# 04-BLE.net
KiCad netlist of a schematic drawn in Altium Designer
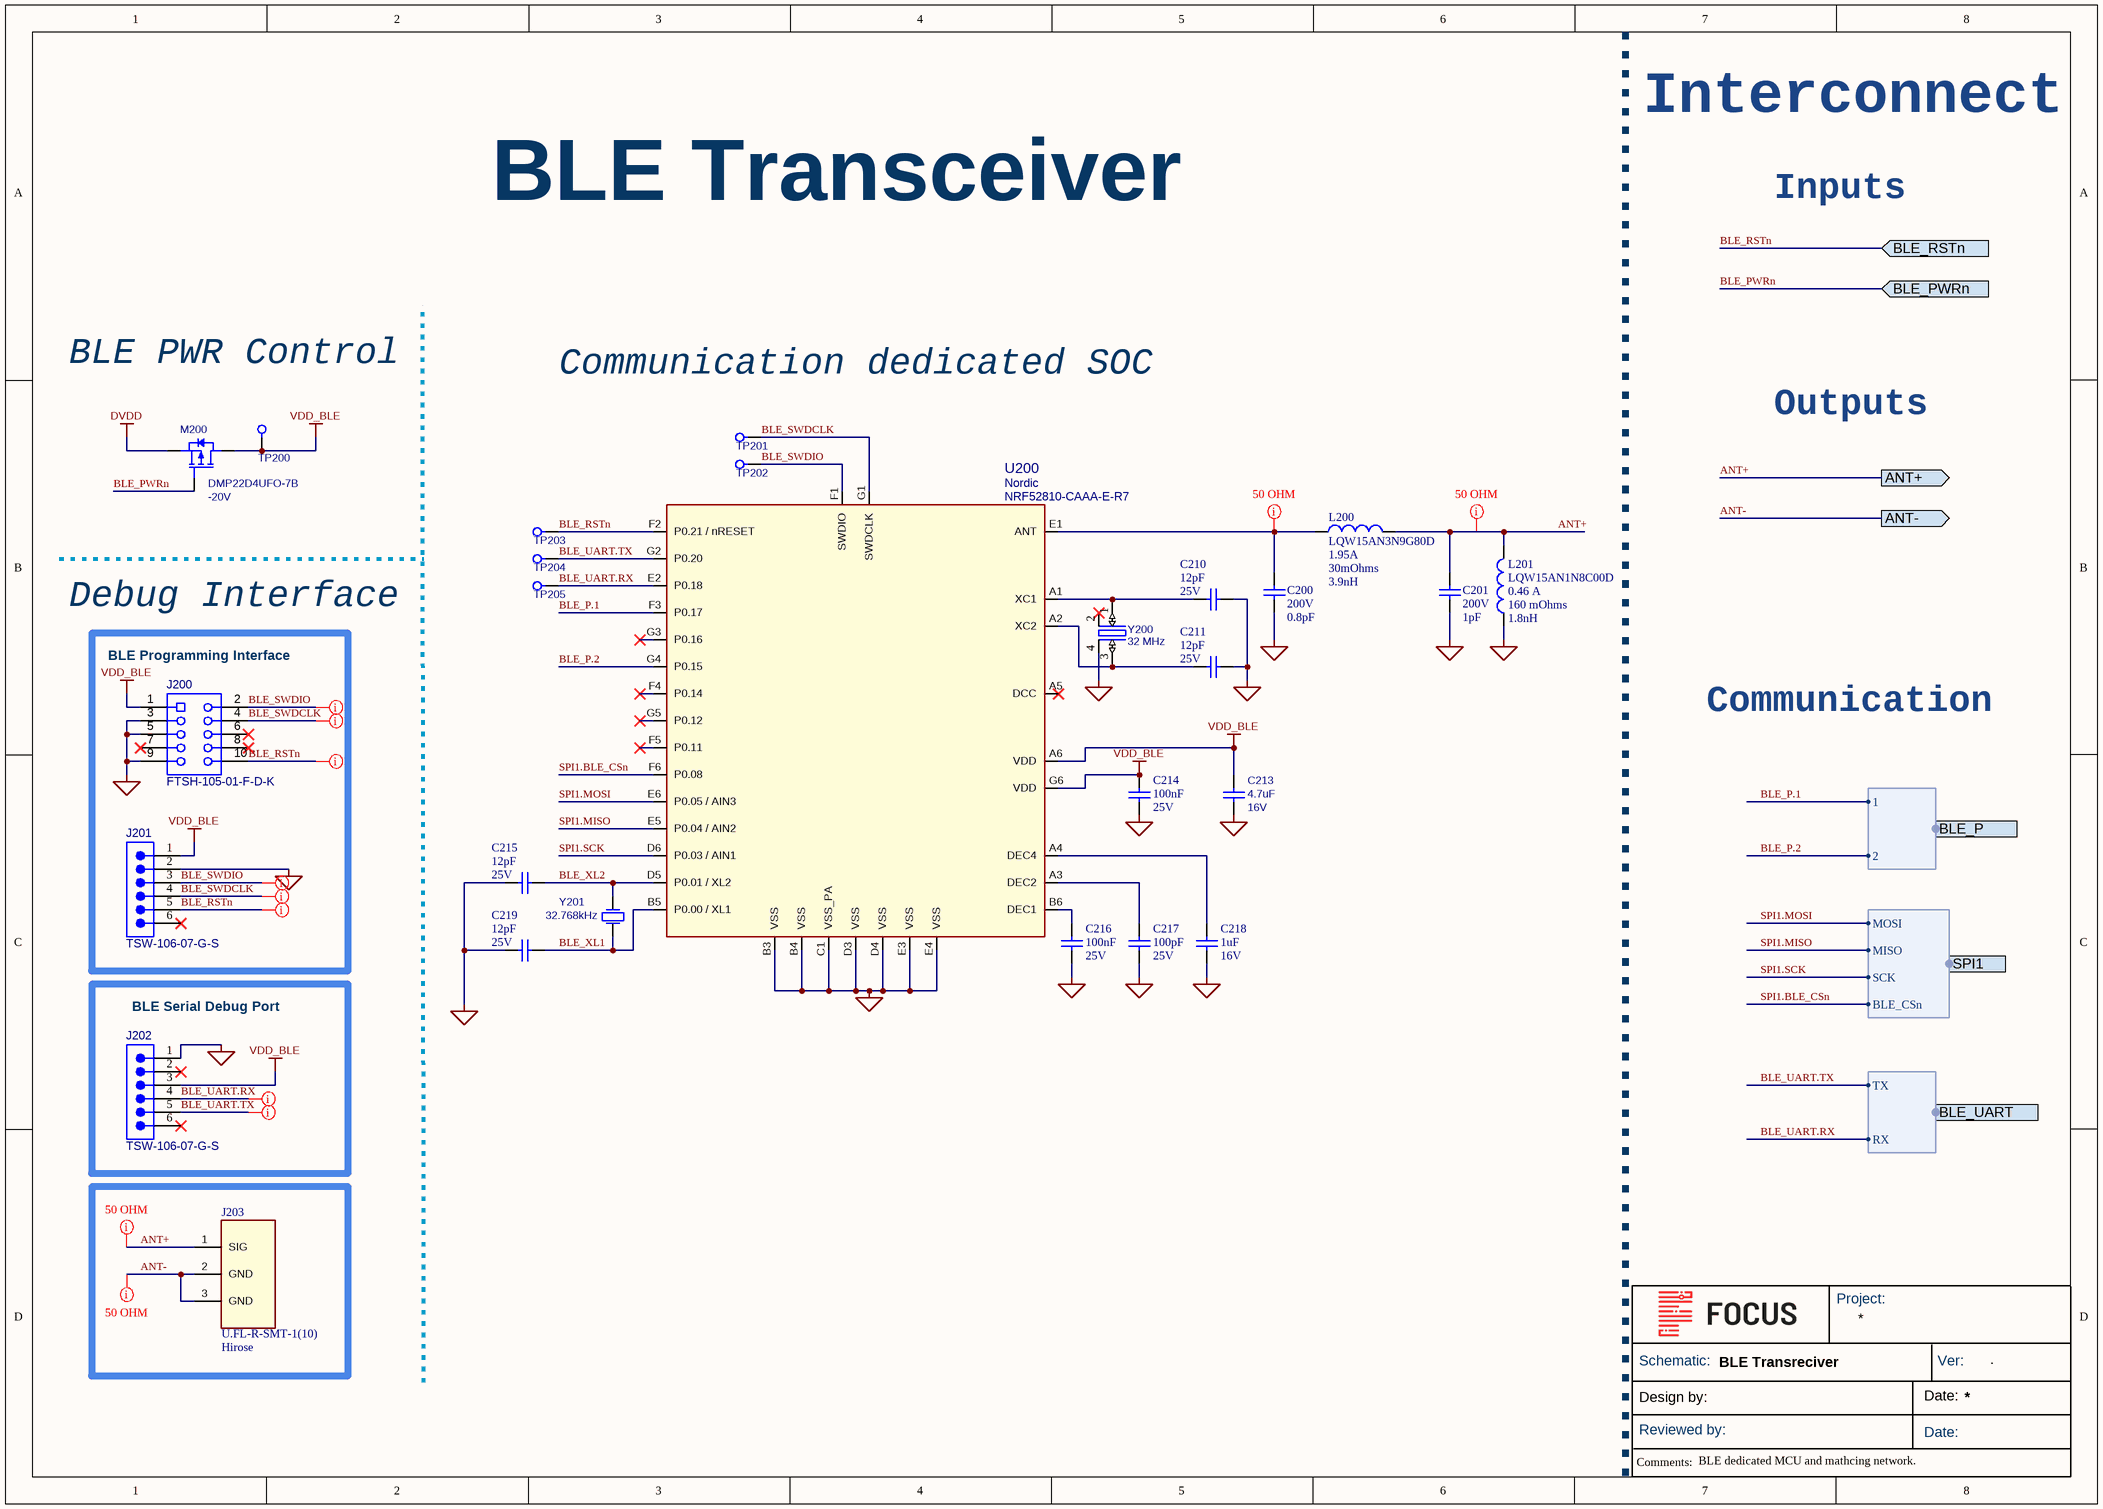
[diagram p0: 04-BLE.SchDoc]

(export (version "E")
  (design (tool "Eeschema 10.0.6"))
  (components
    (comp (ref "C200")
      (value "0.8pF")
      (footprint "CAP0402_REDUCED")
      (description "Capacitor, 0.8pF, Silicon RF, 200V, Tolerance 0.05pF, 0402, Implant-grade")
      (fields
        (field (name "MANUFACTURER") "Kyocera AVX")
        (field (name "MANUFACTURER PART NUMBER") "600L0R8AT200T")
        (field (name "VOLTAGE RATING") "200V")
      )
      (libsource (lib "MP-LIBRARY") (part "600L0R8AT200T"))
    )
    (comp (ref "C201")
      (value "1pF")
      (footprint "CAP0402_REDUCED")
      (description "Capacitor, 1pF, RF Capacitors, 200V, Tolerance 0.01pF, 0402, Implant-grade")
      (fields
        (field (name "MANUFACTURER") "Kyocera AVX")
        (field (name "MANUFACTURER PART NUMBER") "600L1R0AT200T")
        (field (name "VOLTAGE RATING") "200V")
      )
      (libsource (lib "MP-LIBRARY") (part "600L1R0AT200T"))
    )
    (comp (ref "C210")
      (value "12pF")
      (footprint "C0201_C")
      (fields
        (field (name "MANUFACTURER") "Murata")
        (field (name "MANUFACTURER PART NUMBER") "GRM0335C1E120JA01D")
        (field (name "RATED DC VOLTAGE (URDC)") "25V")
      )
      (libsource (lib "MP-LIBRARY") (part "GRM0335C1E120JA01D"))
    )
    (comp (ref "C211")
      (value "12pF")
      (footprint "C0201_C")
      (fields
        (field (name "MANUFACTURER") "Murata")
        (field (name "MANUFACTURER PART NUMBER") "GRM0335C1E120JA01D")
        (field (name "RATED DC VOLTAGE (URDC)") "25V")
      )
      (libsource (lib "MP-LIBRARY") (part "GRM0335C1E120JA01D"))
    )
    (comp (ref "C213")
      (value "4.7uF")
      (footprint "CAP0603_REDUCED")
      (description "Capacitor, 4.7uF, X5R, 16V, 10%, 0603, Implant-grade")
      (fields
        (field (name "MANUFACTURER") "Murata")
        (field (name "RATING") "16V")
        (field (name "MANUFACTURER PART NUMBER") "GRM188R61C475KE11")
      )
      (libsource (lib "MP-LIBRARY") (part "GRM188R61C475KE11"))
    )
    (comp (ref "C214")
      (value "100nF")
      (footprint "C0201_C")
      (fields
        (field (name "MANUFACTURER") "Murata")
        (field (name "MANUFACTURER PART NUMBER") "GRM033R61E104KE14J")
        (field (name "RATED DC VOLTAGE (URDC)") "25V")
      )
      (libsource (lib "MP-LIBRARY") (part "GRM033R61E104KE14J"))
    )
    (comp (ref "C215")
      (value "12pF")
      (footprint "C0201_C")
      (fields
        (field (name "MANUFACTURER") "Murata")
        (field (name "MANUFACTURER PART NUMBER") "GRM0335C1E120JA01D")
        (field (name "RATED DC VOLTAGE (URDC)") "25V")
      )
      (libsource (lib "MP-LIBRARY") (part "GRM0335C1E120JA01D"))
    )
    (comp (ref "C216")
      (value "100nF")
      (footprint "C0201_C")
      (fields
        (field (name "MANUFACTURER") "Murata")
        (field (name "MANUFACTURER PART NUMBER") "GRM033R61E104KE14J")
        (field (name "RATED DC VOLTAGE (URDC)") "25V")
      )
      (libsource (lib "MP-LIBRARY") (part "GRM033R61E104KE14J"))
    )
    (comp (ref "C217")
      (value "100pF")
      (footprint "C0201_C")
      (fields
        (field (name "MANUFACTURER") "Murata")
        (field (name "MANUFACTURER PART NUMBER") "GRM033R71E101KA01D")
        (field (name "RATED DC VOLTAGE (URDC)") "25V")
      )
      (libsource (lib "MP-LIBRARY") (part "GRM033R71E101KA01D"))
    )
    (comp (ref "C218")
      (value "1uF")
      (footprint "C0201_C")
      (fields
        (field (name "MANUFACTURER") "Murata")
        (field (name "MANUFACTURER PART NUMBER") "GRM033R61C105ME15D")
        (field (name "RATED DC VOLTAGE (URDC)") "16V")
      )
      (libsource (lib "MP-LIBRARY") (part "GRM033R61C105ME15D"))
    )
    (comp (ref "C219")
      (value "12pF")
      (footprint "C0201_C")
      (fields
        (field (name "MANUFACTURER") "Murata")
        (field (name "MANUFACTURER PART NUMBER") "GRM0335C1E120JA01D")
        (field (name "RATED DC VOLTAGE (URDC)") "25V")
      )
      (libsource (lib "MP-LIBRARY") (part "GRM0335C1E120JA01D"))
    )
    (comp (ref "J200")
      (value "FTSH-105-01-F-D-K")
      (footprint "SAMTEC_FTSH-105-01-XXX-D-K")
      (description "Connector, 1.27 mm, 2x5, Male, TH")
      (fields (field (name "MANUFACTURER") "Samtec"))
      (libsource (lib "MP-LIBRARY") (part "FTSH-105-01-F-D-K"))
    )
    (comp (ref "J201")
      (value "TSW-106-07-G-S")
      (footprint "SMTC-TSW-106-07-X-S")
      (description "0.025\" SQ Post Header, Through-hole, Vertical, -55 to 125 degC, 2.54 mm Pitch, 6-Pin, Male, RoHS")
      (fields (field (name "MANUFACTURER") "Samtec"))
      (libsource (lib "MP-LIBRARY") (part "TSW-106-07-G-S"))
    )
    (comp (ref "J202")
      (value "TSW-106-07-G-S")
      (footprint "SMTC-TSW-106-07-X-S")
      (description "0.025\" SQ Post Header, Through-hole, Vertical, -55 to 125 degC, 2.54 mm Pitch, 6-Pin, Male, RoHS")
      (fields (field (name "MANUFACTURER") "Samtec"))
      (libsource (lib "MP-LIBRARY") (part "TSW-106-07-G-S"))
    )
    (comp (ref "J203")
      (value "U.FL-R-SMT-1(10)")
      (footprint "FP-U_FL-R-SMT-1_10-MFG")
      (description "RF Connector, 1 Contact(s), Male, Board Mount, Surface Mount Terminal, Receptacle")
      (fields (field (name "MANUFACTURER") "Hirose"))
      (libsource (lib "MP-LIBRARY") (part "U.FL-R-SMT-1(10)"))
    )
    (comp (ref "L200")
      (value "LQW15AN3N9G80D")
      (footprint "L0402_C")
      (description "Inductor, 3.9nH, 1.95A, 2%, 0402")
      (fields
        (field (name "MANUFACTURER") "Murata")
        (field (name "MEDICAL GRADE MANUFACTURER PART NUMBER") "TBD")
        (field (name "CURRENT RATING") "1.95A")
        (field (name "DC RESISTANCE") "30mOhms")
        (field (name "ALTIUM_VALUE") "3.9nH")
      )
      (libsource (lib "MP-LIBRARY") (part "LQW15AN3N9G80D"))
    )
    (comp (ref "L201")
      (value "LQW15AN1N8C00D")
      (footprint "L0402_C")
      (description "Inductor, 1.8nH, 0.46A, Tolerance 0.2 nH, 0402")
      (fields
        (field (name "MANUFACTURER") "Murata")
        (field (name "MEDICAL GRADE MANUFACTURER PART NUMBER") "TBD")
        (field (name "CURRENT RATING") "0.46 A")
        (field (name "DC RESISTANCE") "160 mOhms")
        (field (name "ALTIUM_VALUE") "1.8nH")
      )
      (libsource (lib "MP-LIBRARY") (part "LQW15AN1N8C00D"))
    )
    (comp (ref "M200")
      (value "DMP22D4UFO-7B")
      (footprint "DIODESINC_X2-DFN0604-3")
      (description "MOSFET, P-chan, -20V, -383mA, DFN0604")
      (fields (field (name "MANUFACTURER") "Diodes Inc") (field (name "RATING") "-20V"))
      (libsource (lib "MP-LIBRARY") (part "DMP22D4UFO-7B"))
    )
    (comp (ref "TP200")
      (value "Test Point")
      (footprint "testpad_0.9mm")
      (description "Test pad, 0.90mm circular pad")
      (libsource (lib "MP-LIBRARY") (part "Test Point"))
    )
    (comp (ref "TP201")
      (value "Test Point")
      (footprint "testpad_0.9mm")
      (description "Test pad, 0.90mm circular pad")
      (libsource (lib "MP-LIBRARY") (part "Test Point"))
    )
    (comp (ref "TP202")
      (value "Test Point")
      (footprint "testpad_0.9mm")
      (description "Test pad, 0.90mm circular pad")
      (libsource (lib "MP-LIBRARY") (part "Test Point"))
    )
    (comp (ref "TP203")
      (value "Test Point")
      (footprint "testpad_0.9mm")
      (description "Test pad, 0.90mm circular pad")
      (libsource (lib "MP-LIBRARY") (part "Test Point"))
    )
    (comp (ref "TP204")
      (value "Test Point")
      (footprint "testpad_0.9mm")
      (description "Test pad, 0.90mm circular pad")
      (libsource (lib "MP-LIBRARY") (part "Test Point"))
    )
    (comp (ref "TP205")
      (value "Test Point")
      (footprint "testpad_0.9mm")
      (description "Test pad, 0.90mm circular pad")
      (libsource (lib "MP-LIBRARY") (part "Test Point"))
    )
    (comp (ref "U200")
      (value "NRF52810-CAAA-E-R7")
      (footprint "NORDIC_WLCSP_2.482x2.464")
      (description "Bluetooth radio, v5.0, 192 kB Flash, 24 kB RAM, BGA-33")
      (fields (field (name "MANUFACTURER") "Nordic"))
      (libsource (lib "MP-LIBRARY") (part "NRF52810-CAAA-E-R7"))
    )
    (comp (ref "Y200")
      (value "32 MHz")
      (footprint "XTAL_ECS-SMD-CRYSTAL-10-48-CKY-TR")
      (description "32 MHz Â±10ppm Crystal 10pF 100 Ohms 4-SMD, No Lead")
      (fields
        (field (name "MANUFACTURER") "ECS Inc.")
        (field (name "MANUFACTURER PART NUMBER") "ECS-320-10-48-CKY-TR")
      )
      (libsource (lib "MP-LIBRARY") (part "ECS-320-10-48-CKY-TR"))
    )
    (comp (ref "Y201")
      (value "32.768kHz")
      (footprint "MICROCRYSTAL_CC8V-T1A")
      (description "CRYSTAL 32.7680KHZ 6PF SMD")
      (fields
        (field (name "MANUFACTURER") "Micro Crystal")
        (field (name "MANUFACTURER PART NUMBER") "CM8V-T1A-32.768KHZ-6PF-20PPM-TA-QC")
      )
      (libsource (lib "MP-LIBRARY") (part "CM8V-T1A-32.768KHZ-6PF-20PPM-TA-QC"))
    )
  )
  (nets
    (net (code "5") (name "/ANT+") (class "Default")
      (node (ref "C201") (pin "2") (pinfunction "2_2") (pintype "passive"))
      (node (ref "J203") (pin "1") (pinfunction "SIG_1") (pintype "passive"))
      (node (ref "L200") (pin "2") (pinfunction "2_2") (pintype "passive"))
      (node (ref "L201") (pin "2") (pinfunction "2_2") (pintype "passive"))
    )
    (net (code "6") (name "/ANT-") (class "Default")
      (node (ref "J203") (pin "2") (pinfunction "GND_2") (pintype "passive"))
      (node (ref "J203") (pin "3") (pinfunction "GND_3") (pintype "passive"))
    )
    (net (code "7") (name "/BLE_P.1") (class "Default")
      (node (ref "U200") (pin "F3") (pinfunction "P0.17_F3") (pintype "passive"))
    )
    (net (code "8") (name "/BLE_P.2") (class "Default")
      (node (ref "U200") (pin "G4") (pinfunction "P0.15_G4") (pintype "passive"))
    )
    (net (code "9") (name "/BLE_PWRn") (class "Default")
      (node (ref "M200") (pin "1") (pinfunction "G_1") (pintype "passive"))
    )
    (net (code "10") (name "/BLE_RSTn") (class "Default")
      (node (ref "J200") (pin "10") (pinfunction "10_10") (pintype "passive"))
      (node (ref "J201") (pin "5") (pinfunction "5_5") (pintype "passive"))
      (node (ref "TP203") (pin "1") (pinfunction "1_1") (pintype "passive"))
      (node (ref "U200") (pin "F2") (pinfunction "P0.21_/_nRESET_F2") (pintype "passive"))
    )
    (net (code "11") (name "/BLE_SWDCLK") (class "Default")
      (node (ref "J200") (pin "4") (pinfunction "4_4") (pintype "passive"))
      (node (ref "J201") (pin "4") (pinfunction "4_4") (pintype "passive"))
      (node (ref "TP201") (pin "1") (pinfunction "1_1") (pintype "passive"))
      (node (ref "U200") (pin "G1") (pinfunction "SWDCLK_G1") (pintype "passive"))
    )
    (net (code "12") (name "/BLE_SWDIO") (class "Default")
      (node (ref "J200") (pin "2") (pinfunction "2_2") (pintype "passive"))
      (node (ref "J201") (pin "3") (pinfunction "3_3") (pintype "passive"))
      (node (ref "TP202") (pin "1") (pinfunction "1_1") (pintype "passive"))
      (node (ref "U200") (pin "F1") (pinfunction "SWDIO_F1") (pintype "passive"))
    )
    (net (code "13") (name "/BLE_UART.RX") (class "Default")
      (node (ref "J202") (pin "4") (pinfunction "4_4") (pintype "passive"))
      (node (ref "TP205") (pin "1") (pinfunction "1_1") (pintype "passive"))
      (node (ref "U200") (pin "E2") (pinfunction "P0.18_E2") (pintype "passive"))
    )
    (net (code "14") (name "/BLE_UART.TX") (class "Default")
      (node (ref "J202") (pin "5") (pinfunction "5_5") (pintype "passive"))
      (node (ref "TP204") (pin "1") (pinfunction "1_1") (pintype "passive"))
      (node (ref "U200") (pin "G2") (pinfunction "P0.20_G2") (pintype "passive"))
    )
    (net (code "15") (name "/BLE_XL1") (class "Default")
      (node (ref "C219") (pin "2") (pinfunction "2_2") (pintype "passive"))
      (node (ref "U200") (pin "B5") (pinfunction "P0.00_/_XL1_B5") (pintype "passive"))
      (node (ref "Y201") (pin "1") (pinfunction "1_1") (pintype "passive"))
    )
    (net (code "16") (name "/BLE_XL2") (class "Default")
      (node (ref "C215") (pin "2") (pinfunction "2_2") (pintype "passive"))
      (node (ref "U200") (pin "D5") (pinfunction "P0.01_/_XL2_D5") (pintype "passive"))
      (node (ref "Y201") (pin "2") (pinfunction "2_2") (pintype "passive"))
    )
    (net (code "17") (name "/SPI1.BLE_CSn") (class "Default")
      (node (ref "U200") (pin "F6") (pinfunction "P0.08_F6") (pintype "passive"))
    )
    (net (code "18") (name "/SPI1.MISO") (class "Default")
      (node (ref "U200") (pin "E5") (pinfunction "P0.04_/_AIN2_E5") (pintype "passive"))
    )
    (net (code "19") (name "/SPI1.MOSI") (class "Default")
      (node (ref "U200") (pin "E6") (pinfunction "P0.05_/_AIN3_E6") (pintype "passive"))
    )
    (net (code "20") (name "/SPI1.SCK") (class "Default")
      (node (ref "U200") (pin "D6") (pinfunction "P0.03_/_AIN1_D6") (pintype "passive"))
    )
    (net (code "24") (name "DVDD") (class "Default")
      (node (ref "M200") (pin "2") (pinfunction "S_2") (pintype "passive"))
    )
    (net (code "25") (name "GND") (class "Default")
      (node (ref "C200") (pin "1") (pinfunction "1_1") (pintype "passive"))
      (node (ref "C201") (pin "1") (pinfunction "1_1") (pintype "passive"))
      (node (ref "C210") (pin "2") (pinfunction "2_2") (pintype "passive"))
      (node (ref "C211") (pin "2") (pinfunction "2_2") (pintype "passive"))
      (node (ref "C213") (pin "2") (pinfunction "2_2") (pintype "passive"))
      (node (ref "C214") (pin "1") (pinfunction "1_1") (pintype "passive"))
      (node (ref "C215") (pin "1") (pinfunction "1_1") (pintype "passive"))
      (node (ref "C216") (pin "1") (pinfunction "1_1") (pintype "passive"))
      (node (ref "C217") (pin "1") (pinfunction "1_1") (pintype "passive"))
      (node (ref "C218") (pin "2") (pinfunction "2_2") (pintype "passive"))
      (node (ref "C219") (pin "1") (pinfunction "1_1") (pintype "passive"))
      (node (ref "J200") (pin "3") (pinfunction "3_3") (pintype "passive"))
      (node (ref "J200") (pin "5") (pinfunction "5_5") (pintype "passive"))
      (node (ref "J200") (pin "9") (pinfunction "9_9") (pintype "passive"))
      (node (ref "J201") (pin "2") (pinfunction "2_2") (pintype "passive"))
      (node (ref "J202") (pin "1") (pinfunction "1_1") (pintype "passive"))
      (node (ref "L201") (pin "1") (pinfunction "1_1") (pintype "passive"))
      (node (ref "U200") (pin "B3") (pinfunction "VSS_B3") (pintype "passive"))
      (node (ref "U200") (pin "B4") (pinfunction "VSS_B4") (pintype "passive"))
      (node (ref "U200") (pin "C1") (pinfunction "VSS_PA_C1") (pintype "passive"))
      (node (ref "U200") (pin "D3") (pinfunction "VSS_D3") (pintype "passive"))
      (node (ref "U200") (pin "D4") (pinfunction "VSS_D4") (pintype "passive"))
      (node (ref "U200") (pin "E3") (pinfunction "VSS_E3") (pintype "passive"))
      (node (ref "U200") (pin "E4") (pinfunction "VSS_E4") (pintype "passive"))
      (node (ref "Y200") (pin "4") (pinfunction "GND_4") (pintype "passive"))
    )
    (net (code "26") (name "Net-(U200-ANT)") (class "Default")
      (node (ref "C200") (pin "2") (pinfunction "2_2") (pintype "passive"))
      (node (ref "L200") (pin "1") (pinfunction "1_1") (pintype "passive"))
      (node (ref "U200") (pin "E1") (pinfunction "ANT_E1") (pintype "passive"))
    )
    (net (code "27") (name "Net-(U200-DEC1)") (class "Default")
      (node (ref "C216") (pin "2") (pinfunction "2_2") (pintype "passive"))
      (node (ref "U200") (pin "B6") (pinfunction "DEC1_B6") (pintype "passive"))
    )
    (net (code "28") (name "Net-(U200-DEC2)") (class "Default")
      (node (ref "C217") (pin "2") (pinfunction "2_2") (pintype "passive"))
      (node (ref "U200") (pin "A3") (pinfunction "DEC2_A3") (pintype "passive"))
    )
    (net (code "29") (name "Net-(U200-DEC4)") (class "Default")
      (node (ref "C218") (pin "1") (pinfunction "1_1") (pintype "passive"))
      (node (ref "U200") (pin "A4") (pinfunction "DEC4_A4") (pintype "passive"))
    )
    (net (code "30") (name "Net-(U200-XC1)") (class "Default")
      (node (ref "C210") (pin "1") (pinfunction "1_1") (pintype "passive"))
      (node (ref "U200") (pin "A1") (pinfunction "XC1_A1") (pintype "passive"))
      (node (ref "Y200") (pin "1") (pinfunction "IN/OUT_1") (pintype "bidirectional"))
    )
    (net (code "31") (name "Net-(U200-XC2)") (class "Default")
      (node (ref "C211") (pin "1") (pinfunction "1_1") (pintype "passive"))
      (node (ref "U200") (pin "A2") (pinfunction "XC2_A2") (pintype "passive"))
      (node (ref "Y200") (pin "3") (pinfunction "OUT/IN_3") (pintype "bidirectional"))
    )
    (net (code "32") (name "VDD_BLE") (class "Default")
      (node (ref "C213") (pin "1") (pinfunction "1_1") (pintype "passive"))
      (node (ref "C214") (pin "2") (pinfunction "2_2") (pintype "passive"))
      (node (ref "J200") (pin "1") (pinfunction "1_1") (pintype "passive"))
      (node (ref "J201") (pin "1") (pinfunction "1_1") (pintype "passive"))
      (node (ref "J202") (pin "3") (pinfunction "3_3") (pintype "passive"))
      (node (ref "M200") (pin "3") (pinfunction "D_3") (pintype "passive"))
      (node (ref "TP200") (pin "1") (pinfunction "1_1") (pintype "passive"))
      (node (ref "U200") (pin "A6") (pinfunction "VDD_A6") (pintype "passive"))
      (node (ref "U200") (pin "G6") (pinfunction "VDD_G6") (pintype "passive"))
    )
    (net (code "33") (name "unconnected-(J200-Pad6)") (class "Default")
      (node (ref "J200") (pin "6") (pinfunction "6_6") (pintype "passive+no_connect"))
    )
    (net (code "34") (name "unconnected-(J200-Pad7)") (class "Default")
      (node (ref "J200") (pin "7") (pinfunction "7_7") (pintype "passive+no_connect"))
    )
    (net (code "35") (name "unconnected-(J200-Pad8)") (class "Default")
      (node (ref "J200") (pin "8") (pinfunction "8_8") (pintype "passive+no_connect"))
    )
    (net (code "36") (name "unconnected-(J201-Pad6)") (class "Default")
      (node (ref "J201") (pin "6") (pinfunction "6_6") (pintype "passive+no_connect"))
    )
    (net (code "37") (name "unconnected-(J202-Pad2)") (class "Default")
      (node (ref "J202") (pin "2") (pinfunction "2_2") (pintype "passive+no_connect"))
    )
    (net (code "38") (name "unconnected-(J202-Pad6)") (class "Default")
      (node (ref "J202") (pin "6") (pinfunction "6_6") (pintype "passive+no_connect"))
    )
    (net (code "39") (name "unconnected-(U200-DCC-PadA5)") (class "Default")
      (node (ref "U200") (pin "A5") (pinfunction "DCC_A5") (pintype "passive+no_connect"))
    )
    (net (code "40") (name "unconnected-(U200-P0.11-PadF5)") (class "Default")
      (node (ref "U200") (pin "F5") (pinfunction "P0.11_F5") (pintype "passive+no_connect"))
    )
    (net (code "41") (name "unconnected-(U200-P0.12-PadG5)") (class "Default")
      (node (ref "U200") (pin "G5") (pinfunction "P0.12_G5") (pintype "passive+no_connect"))
    )
    (net (code "42") (name "unconnected-(U200-P0.14-PadF4)") (class "Default")
      (node (ref "U200") (pin "F4") (pinfunction "P0.14_F4") (pintype "passive+no_connect"))
    )
    (net (code "43") (name "unconnected-(U200-P0.16-PadG3)") (class "Default")
      (node (ref "U200") (pin "G3") (pinfunction "P0.16_G3") (pintype "passive+no_connect"))
    )
    (net (code "44") (name "unconnected-(Y200-NC-Pad2)") (class "Default")
      (node (ref "Y200") (pin "2") (pinfunction "NC_2") (pintype "passive+no_connect"))
    )
  )
)
